# DC25_HHV_RE-A.net
KiCad netlist of a schematic drawn in EAGLE
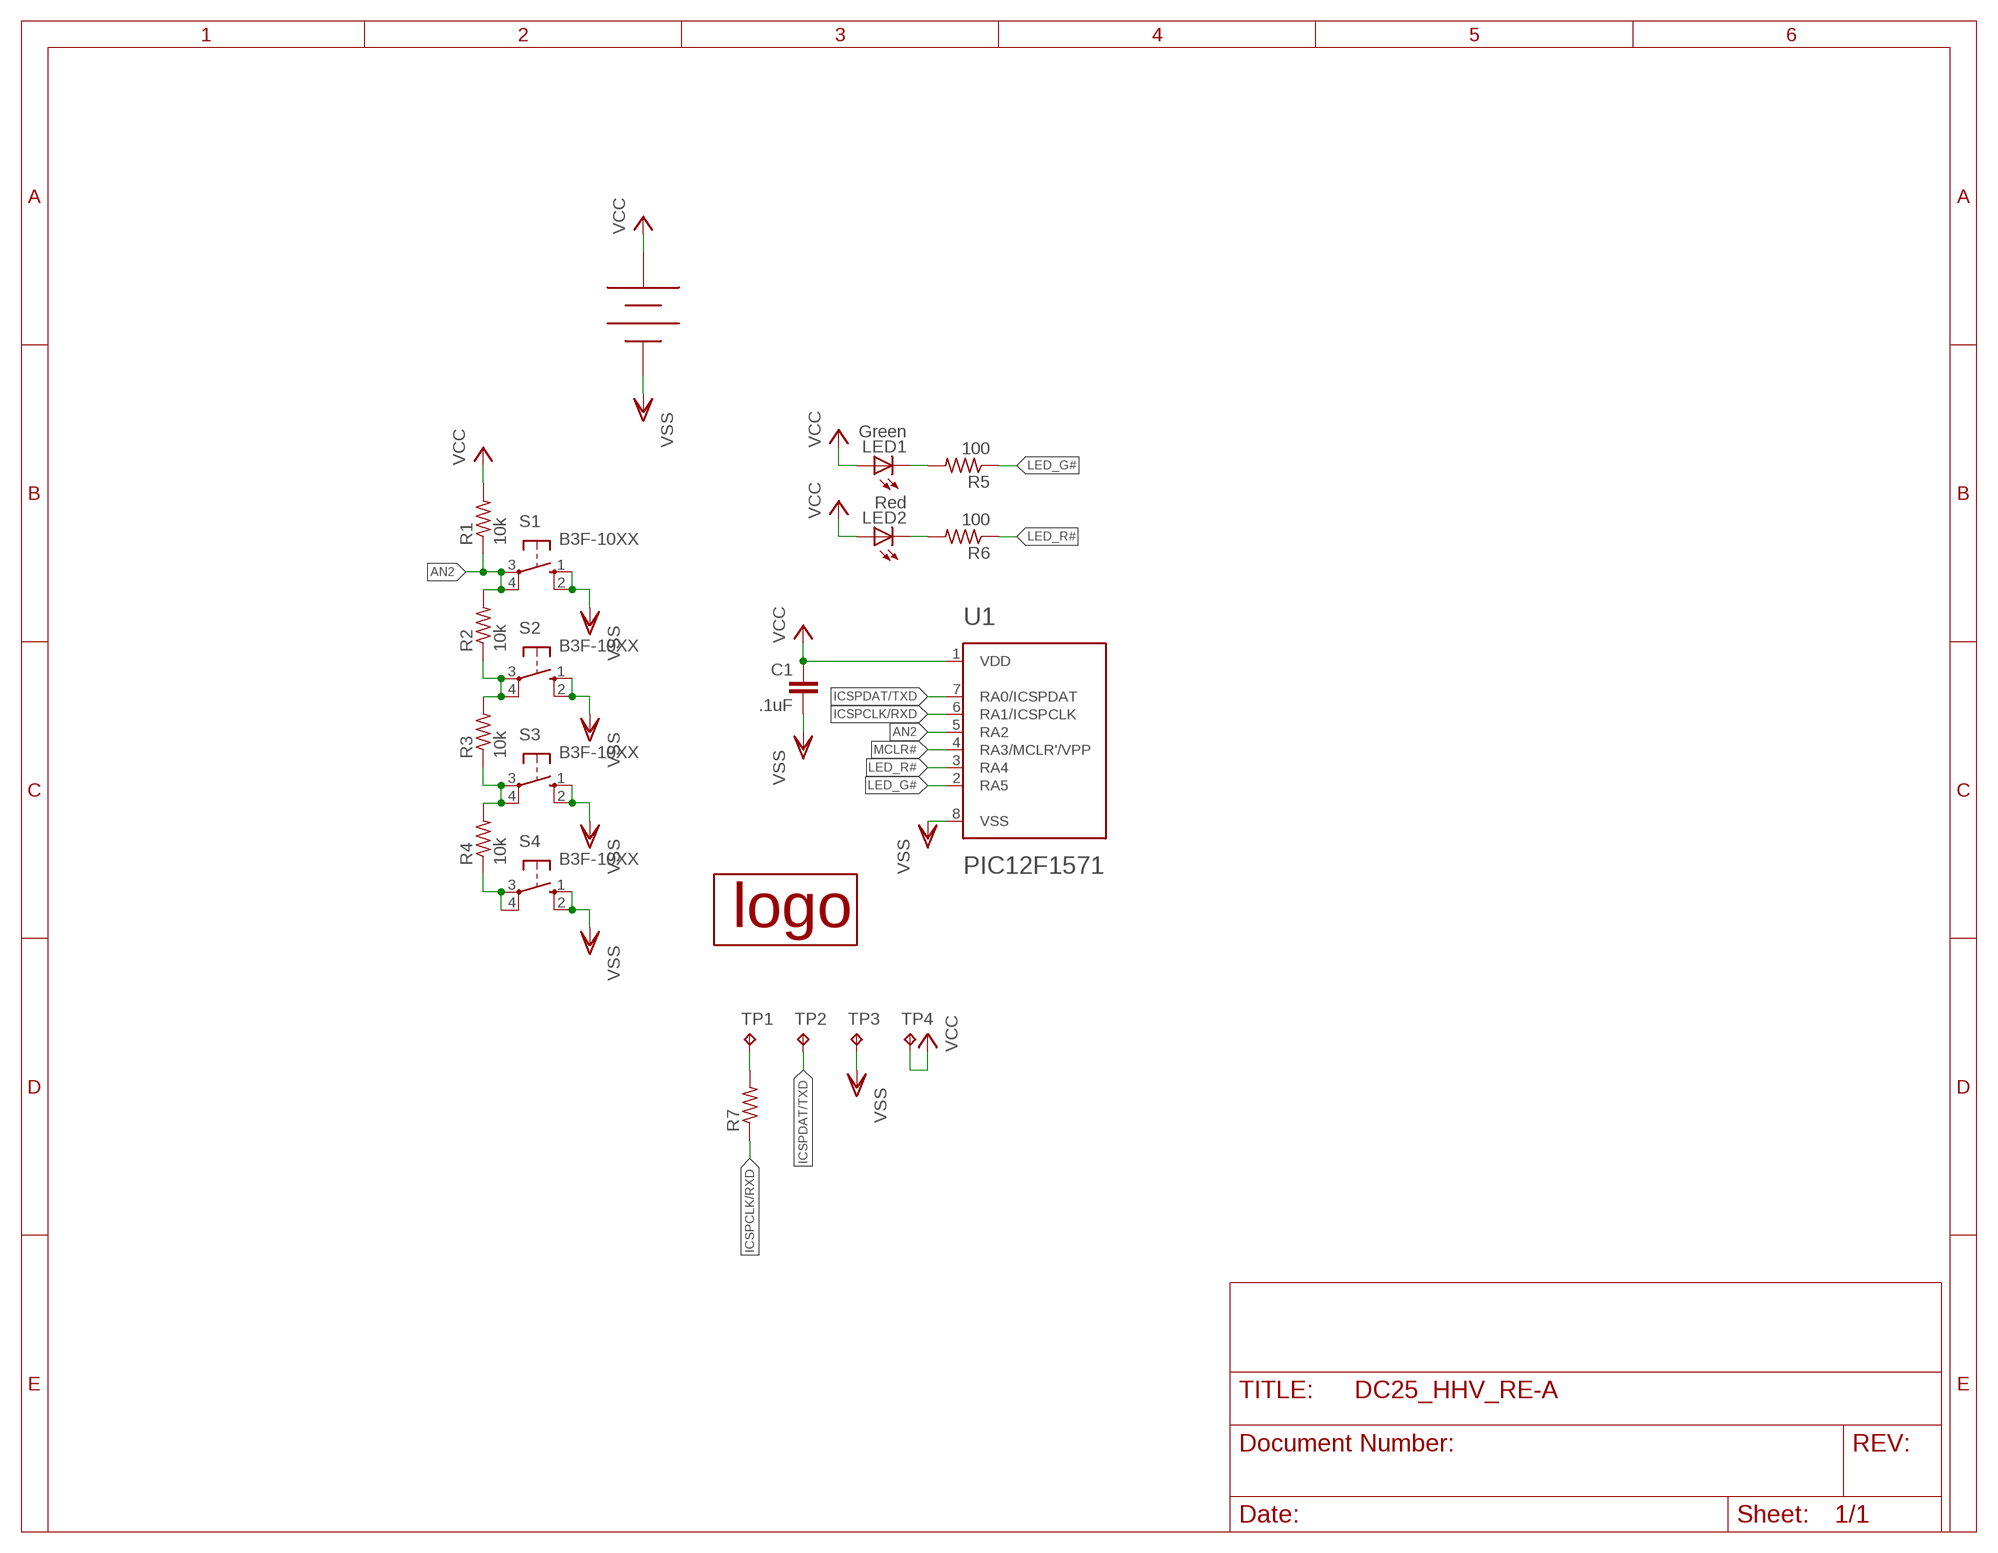
[diagram p0: schematic, sheet 1]

(export (version "E")
  (design (tool "Eeschema 10.0.6"))
  (components
    (comp (ref "BT1")
      (value "BAT-HLD-001-THM")
      (footprint "eagle-import:BAT-HLD-001-THM")
      (libsource (lib "eagle-import") (part "BAT-HLD-001-THM"))
    )
    (comp (ref "C1")
      (value ".1uF")
      (footprint "eagle-import:C050-024X044")
      (libsource (lib "eagle-import") (part "C-EU050-024X044"))
    )
    (comp (ref "LED1")
      (value "Green")
      (footprint "eagle-import:LED5MM")
      (libsource (lib "eagle-import") (part "LED5MM"))
    )
    (comp (ref "LED2")
      (value "Red")
      (footprint "eagle-import:LED5MM")
      (libsource (lib "eagle-import") (part "LED5MM"))
    )
    (comp (ref "R1")
      (value "10k")
      (footprint "eagle-import:0207_10")
      (libsource (lib "eagle-import") (part "R-US_0207/10"))
    )
    (comp (ref "R2")
      (value "10k")
      (footprint "eagle-import:0207_10")
      (libsource (lib "eagle-import") (part "R-US_0207/10"))
    )
    (comp (ref "R3")
      (value "10k")
      (footprint "eagle-import:0207_10")
      (libsource (lib "eagle-import") (part "R-US_0207/10"))
    )
    (comp (ref "R4")
      (value "10k")
      (footprint "eagle-import:0207_10")
      (libsource (lib "eagle-import") (part "R-US_0207/10"))
    )
    (comp (ref "R5")
      (value "100")
      (footprint "eagle-import:0207_10")
      (libsource (lib "eagle-import") (part "R-US_0207/10"))
    )
    (comp (ref "R6")
      (value "100")
      (footprint "eagle-import:0207_10")
      (libsource (lib "eagle-import") (part "R-US_0207/10"))
    )
    (comp (ref "R7")
      (value "R-US_R0402")
      (footprint "eagle-import:R0402")
      (libsource (lib "eagle-import") (part "R-US_R0402"))
    )
    (comp (ref "S1")
      (value "B3F-10XX")
      (footprint "eagle-import:B3F-10XX")
      (fields (field (name "MPN") "B3F-1000"))
      (libsource (lib "eagle-import") (part "10-XX"))
    )
    (comp (ref "S2")
      (value "B3F-10XX")
      (footprint "eagle-import:B3F-10XX")
      (fields (field (name "MPN") "B3F-1000"))
      (libsource (lib "eagle-import") (part "10-XX"))
    )
    (comp (ref "S3")
      (value "B3F-10XX")
      (footprint "eagle-import:B3F-10XX")
      (fields (field (name "MPN") "B3F-1000"))
      (libsource (lib "eagle-import") (part "10-XX"))
    )
    (comp (ref "S4")
      (value "B3F-10XX")
      (footprint "eagle-import:B3F-10XX")
      (fields (field (name "MPN") "B3F-1000"))
      (libsource (lib "eagle-import") (part "10-XX"))
    )
    (comp (ref "TP1")
      (value "TPTP13R")
      (footprint "eagle-import:TP13R")
      (libsource (lib "eagle-import") (part "TPTP13R"))
    )
    (comp (ref "TP2")
      (value "TPTP13R")
      (footprint "eagle-import:TP13R")
      (libsource (lib "eagle-import") (part "TPTP13R"))
    )
    (comp (ref "TP3")
      (value "TPTP13R")
      (footprint "eagle-import:TP13R")
      (libsource (lib "eagle-import") (part "TPTP13R"))
    )
    (comp (ref "TP4")
      (value "TPTP13R")
      (footprint "eagle-import:TP13R")
      (libsource (lib "eagle-import") (part "TPTP13R"))
    )
    (comp (ref "U$1")
      (value "KBELOGO-SILK")
      (footprint "eagle-import:KBELOGO-SILK")
      (libsource (lib "eagle-import") (part "KBELOGO-SILK"))
    )
    (comp (ref "U1")
      (value "PIC12F1571")
      (footprint "eagle-import:DIL8")
      (libsource (lib "eagle-import") (part "PIC12F1571"))
    )
  )
  (nets
    (net (code "1") (name "AN2") (class "Default")
      (node (ref "R1") (pin "1") (pinfunction "1_1") (pintype "passive"))
      (node (ref "R2") (pin "2") (pinfunction "2_2") (pintype "passive"))
      (node (ref "S1") (pin "3") (pinfunction "P_3") (pintype "passive"))
      (node (ref "S1") (pin "4") (pinfunction "P1_4") (pintype "passive"))
      (node (ref "U1") (pin "5") (pinfunction "RA2_5") (pintype "bidirectional"))
    )
    (net (code "2") (name "ICSPCLK{slash}RXD") (class "Default")
      (node (ref "R7") (pin "1") (pinfunction "1_1") (pintype "passive"))
      (node (ref "U1") (pin "6") (pinfunction "RA1/ICSPCLK_6") (pintype "bidirectional"))
    )
    (net (code "3") (name "ICSPDAT{slash}TXD") (class "Default")
      (node (ref "TP2") (pin "TP") (pinfunction "TP_TP") (pintype "input"))
      (node (ref "U1") (pin "7") (pinfunction "RA0/ICSPDAT_7") (pintype "bidirectional"))
    )
    (net (code "4") (name "LED_G#") (class "Default")
      (node (ref "R5") (pin "1") (pinfunction "1_1") (pintype "passive"))
      (node (ref "U1") (pin "2") (pinfunction "RA5_2") (pintype "bidirectional"))
    )
    (net (code "5") (name "LED_R#") (class "Default")
      (node (ref "R6") (pin "1") (pinfunction "1_1") (pintype "passive"))
      (node (ref "U1") (pin "3") (pinfunction "RA4_3") (pintype "bidirectional"))
    )
    (net (code "6") (name "MCLR#") (class "Default")
      (node (ref "U1") (pin "4") (pinfunction "RA3/MCLR'/VPP_4") (pintype "bidirectional"))
    )
    (net (code "7") (name "Net-(LED1-C)") (class "Default")
      (node (ref "LED1") (pin "K") (pinfunction "C_K") (pintype "passive"))
      (node (ref "R5") (pin "2") (pinfunction "2_2") (pintype "passive"))
    )
    (net (code "8") (name "Net-(LED2-C)") (class "Default")
      (node (ref "LED2") (pin "K") (pinfunction "C_K") (pintype "passive"))
      (node (ref "R6") (pin "2") (pinfunction "2_2") (pintype "passive"))
    )
    (net (code "9") (name "Net-(R7-Pad2)") (class "Default")
      (node (ref "R7") (pin "2") (pinfunction "2_2") (pintype "passive"))
      (node (ref "TP1") (pin "TP") (pinfunction "TP_TP") (pintype "input"))
    )
    (net (code "10") (name "Net-(S2-P)") (class "Default")
      (node (ref "R2") (pin "1") (pinfunction "1_1") (pintype "passive"))
      (node (ref "R3") (pin "2") (pinfunction "2_2") (pintype "passive"))
      (node (ref "S2") (pin "3") (pinfunction "P_3") (pintype "passive"))
      (node (ref "S2") (pin "4") (pinfunction "P1_4") (pintype "passive"))
    )
    (net (code "11") (name "Net-(S3-P)") (class "Default")
      (node (ref "R3") (pin "1") (pinfunction "1_1") (pintype "passive"))
      (node (ref "R4") (pin "2") (pinfunction "2_2") (pintype "passive"))
      (node (ref "S3") (pin "3") (pinfunction "P_3") (pintype "passive"))
      (node (ref "S3") (pin "4") (pinfunction "P1_4") (pintype "passive"))
    )
    (net (code "12") (name "Net-(S4-P)") (class "Default")
      (node (ref "R4") (pin "1") (pinfunction "1_1") (pintype "passive"))
      (node (ref "S4") (pin "3") (pinfunction "P_3") (pintype "passive"))
      (node (ref "S4") (pin "4") (pinfunction "P1_4") (pintype "passive"))
    )
    (net (code "13") (name "VCC") (class "Default")
      (node (ref "BT1") (pin "+@0") (pinfunction "VCC_+@0") (pintype "bidirectional"))
      (node (ref "BT1") (pin "+@1") (pinfunction "VCC_+@1") (pintype "bidirectional"))
      (node (ref "BT1") (pin "+@2") (pinfunction "VCC_+@2") (pintype "bidirectional"))
      (node (ref "BT1") (pin "+@3") (pinfunction "VCC_+@3") (pintype "bidirectional"))
      (node (ref "C1") (pin "1") (pinfunction "1_1") (pintype "passive"))
      (node (ref "LED1") (pin "A") (pinfunction "A_A") (pintype "passive"))
      (node (ref "LED2") (pin "A") (pinfunction "A_A") (pintype "passive"))
      (node (ref "R1") (pin "2") (pinfunction "2_2") (pintype "passive"))
      (node (ref "TP4") (pin "TP") (pinfunction "TP_TP") (pintype "input"))
      (node (ref "U1") (pin "1") (pinfunction "VDD_1") (pintype "power_in"))
    )
    (net (code "14") (name "VSS") (class "Default")
      (node (ref "BT1") (pin "-") (pinfunction "VSS_-") (pintype "bidirectional"))
      (node (ref "C1") (pin "2") (pinfunction "2_2") (pintype "passive"))
      (node (ref "S1") (pin "1") (pinfunction "S_1") (pintype "passive"))
      (node (ref "S1") (pin "2") (pinfunction "S1_2") (pintype "passive"))
      (node (ref "S2") (pin "1") (pinfunction "S_1") (pintype "passive"))
      (node (ref "S2") (pin "2") (pinfunction "S1_2") (pintype "passive"))
      (node (ref "S3") (pin "1") (pinfunction "S_1") (pintype "passive"))
      (node (ref "S3") (pin "2") (pinfunction "S1_2") (pintype "passive"))
      (node (ref "S4") (pin "1") (pinfunction "S_1") (pintype "passive"))
      (node (ref "S4") (pin "2") (pinfunction "S1_2") (pintype "passive"))
      (node (ref "TP3") (pin "TP") (pinfunction "TP_TP") (pintype "input"))
      (node (ref "U1") (pin "8") (pinfunction "VSS_8") (pintype "power_in"))
    )
  )
)
